# MC-34063.net
KiCad netlist of a schematic drawn in Altium Designer
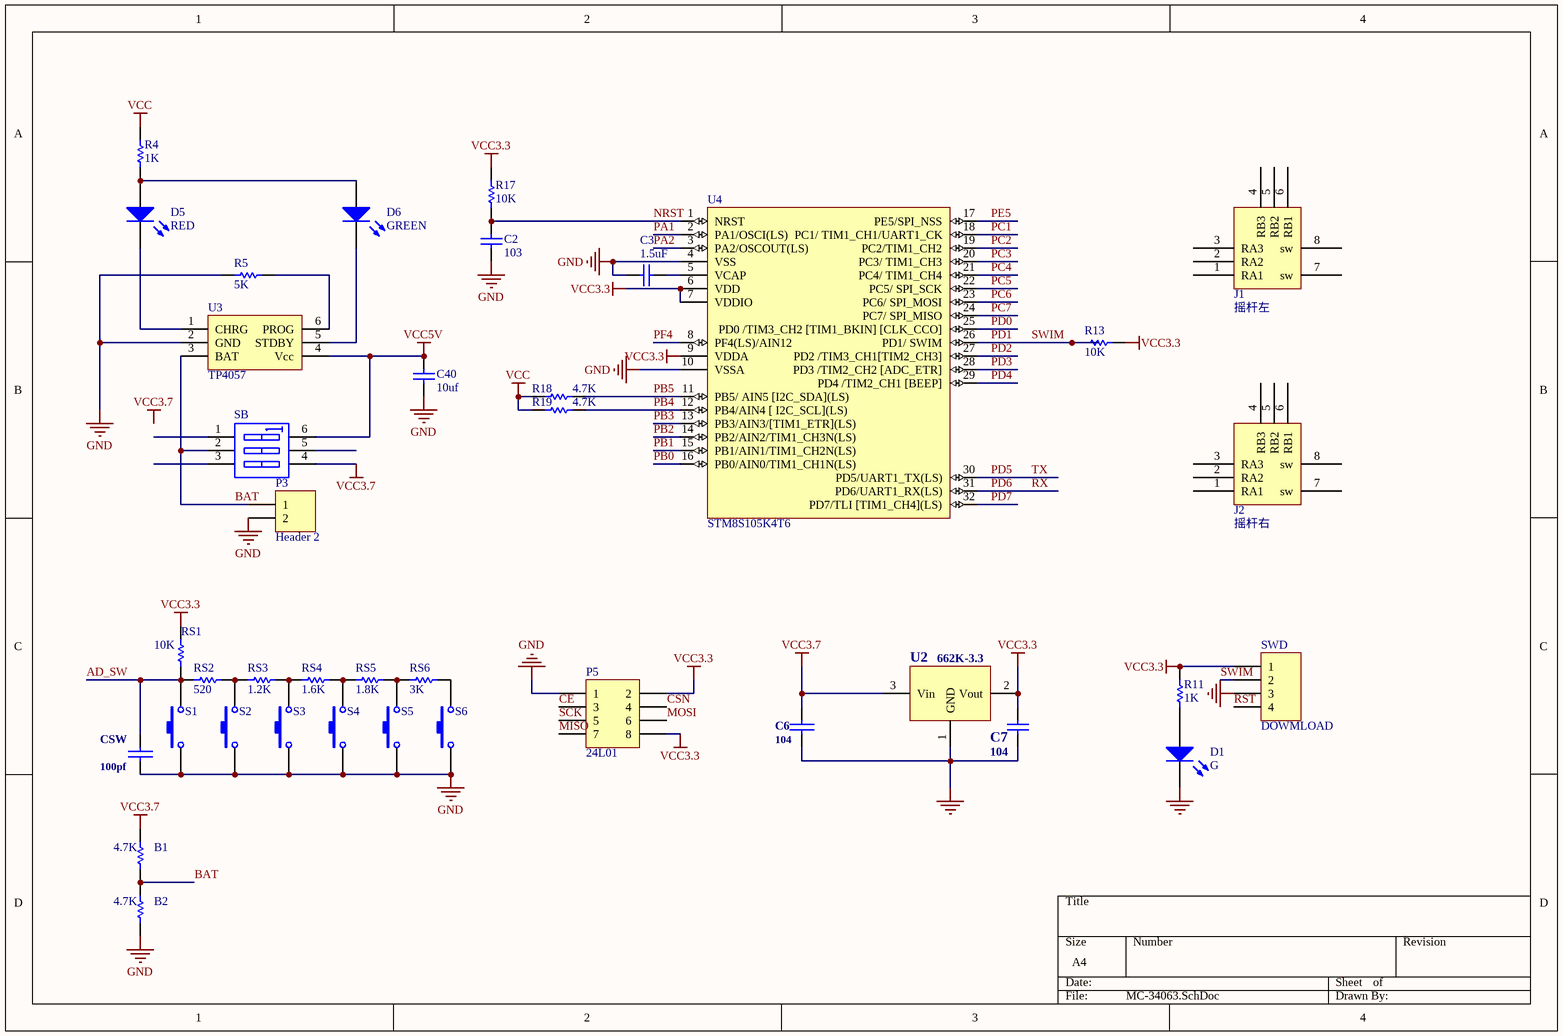
[diagram p0: MC-34063.SchDoc]

(export (version "E")
  (design (tool "Eeschema 10.0.6"))
  (components
    (comp (ref "B1")
      (value "4.7K")
      (footprint "6-0805_L")
      (description "Resistor")
      (fields (field (name "Comment") "Res1") (field (name "PUBLISHER") "Altium Limited"))
      (libsource (lib "Miscellaneous Devices") (part "Res1"))
    )
    (comp (ref "B2")
      (value "4.7K")
      (footprint "6-0805_L")
      (description "Resistor")
      (fields (field (name "Comment") "Res1") (field (name "PUBLISHER") "Altium Limited"))
      (libsource (lib "Miscellaneous Devices") (part "Res1"))
    )
    (comp (ref "C2")
      (value "103")
      (footprint "CAPC2012L")
      (description "Capacitor")
      (fields (field (name "Comment") "Cap") (field (name "PUBLISHER") "Altium Limited"))
      (libsource (lib "Miscellaneous Devices") (part "Cap"))
    )
    (comp (ref "C3")
      (value "1.5uF")
      (footprint "CAPC2012L")
      (description "Capacitor")
      (fields (field (name "Comment") "Cap") (field (name "PUBLISHER") "Altium Limited"))
      (libsource (lib "Miscellaneous Devices") (part "Cap"))
    )
    (comp (ref "C6")
      (value "104")
      (footprint "6-0805_L")
      (description "Capacitor")
      (libsource (lib "*") (part "CAP"))
    )
    (comp (ref "C7")
      (value "104")
      (footprint "6-0805_l")
      (description "Capacitor")
      (libsource (lib "*") (part "Cap"))
    )
    (comp (ref "C40")
      (value "10uf")
      (footprint "CAPC2012L")
      (description "Capacitor")
      (fields (field (name "Comment") "Cap") (field (name "PUBLISHER") "Altium Limited"))
      (libsource (lib "Miscellaneous Devices") (part "Cap"))
    )
    (comp (ref "CSW")
      (value "100pf")
      (footprint "6-0805_L")
      (description "Capacitor")
      (libsource (lib "*") (part "CAP"))
    )
    (comp (ref "D1")
      (value "G")
      (footprint "6-0805_L")
      (description "Typical BLUE SiC LED")
      (fields (field (name "PUBLISHER") "Altium Limited"))
      (libsource (lib "Miscellaneous Devices") (part "LED3"))
    )
    (comp (ref "D5")
      (value "RED")
      (footprint "CD2012-0805")
      (description "Typical BLUE SiC LED")
      (fields (field (name "PUBLISHER") "Altium Limited"))
      (libsource (lib "Miscellaneous Devices") (part "LED3"))
    )
    (comp (ref "D6")
      (value "GREEN")
      (footprint "CD2012-0805")
      (description "Typical BLUE SiC LED")
      (fields (field (name "PUBLISHER") "Altium Limited"))
      (libsource (lib "Miscellaneous Devices") (part "LED3"))
    )
    (comp (ref "J1") (value "摇杆左") (footprint "摇杆") (libsource (lib "摇杆原理图") (part "Component_1")))
    (comp (ref "J2") (value "摇杆右") (footprint "摇杆") (libsource (lib "摇杆原理图") (part "Component_1")))
    (comp (ref "P3")
      (value "Header 2")
      (footprint "HDR1X2")
      (description "Header, 2-Pin")
      (fields (field (name "PUBLISHER") "Altium Limited"))
      (libsource (lib "Miscellaneous Connectors") (part "Header 2"))
    )
    (comp (ref "P5")
      (value "24L01")
      (footprint "HDR2X4")
      (description "Header, 4-Pin, Dual row")
      (fields (field (name "PUBLISHER") "Altium Limited"))
      (libsource (lib "Miscellaneous Connectors") (part "Header 4X2"))
    )
    (comp (ref "R4")
      (value "1K")
      (footprint "RESC2012L")
      (description "Resistor")
      (fields (field (name "Comment") "Res1") (field (name "PUBLISHER") "Altium Limited"))
      (libsource (lib "Miscellaneous Devices") (part "Res1"))
    )
    (comp (ref "R5")
      (value "5K")
      (footprint "RESC2012L")
      (description "Resistor")
      (fields (field (name "Comment") "Res1") (field (name "PUBLISHER") "Altium Limited"))
      (libsource (lib "Miscellaneous Devices") (part "Res1"))
    )
    (comp (ref "R11")
      (value "1K")
      (footprint "6-0805_L")
      (description "Resistor")
      (fields (field (name "Comment") "Res1") (field (name "PUBLISHER") "Altium Limited"))
      (libsource (lib "Miscellaneous Devices") (part "Res1"))
    )
    (comp (ref "R13")
      (value "10K")
      (footprint "6-0805_L")
      (description "Resistor")
      (fields (field (name "Comment") "Res1") (field (name "PUBLISHER") "Altium Limited"))
      (libsource (lib "Miscellaneous Devices") (part "Res1"))
    )
    (comp (ref "R17")
      (value "10K")
      (footprint "RESC2012L")
      (description "Resistor")
      (fields (field (name "Comment") "Res1") (field (name "PUBLISHER") "Altium Limited"))
      (libsource (lib "Miscellaneous Devices") (part "Res1"))
    )
    (comp (ref "R18")
      (value "4.7K")
      (footprint "resc2012l")
      (description "Resistor")
      (fields (field (name "Comment") "Res1") (field (name "PUBLISHER") "Altium Limited"))
      (libsource (lib "Miscellaneous Devices") (part "Res1"))
    )
    (comp (ref "R19")
      (value "4.7K")
      (footprint "resc2012l")
      (description "Resistor")
      (fields (field (name "Comment") "Res1") (field (name "PUBLISHER") "Altium Limited"))
      (libsource (lib "Miscellaneous Devices") (part "Res1"))
    )
    (comp (ref "RS1")
      (value "10K")
      (footprint "6-0805_L")
      (description "Resistor")
      (fields (field (name "Comment") "Res1") (field (name "PUBLISHER") "Altium Limited"))
      (libsource (lib "Miscellaneous Devices") (part "Res1"))
    )
    (comp (ref "RS2")
      (value "520")
      (footprint "6-0805_L")
      (description "Resistor")
      (fields (field (name "Comment") "Res1") (field (name "PUBLISHER") "Altium Limited"))
      (libsource (lib "Miscellaneous Devices") (part "Res1"))
    )
    (comp (ref "RS3")
      (value "1.2K")
      (footprint "6-0805_L")
      (description "Resistor")
      (fields (field (name "Comment") "Res1") (field (name "PUBLISHER") "Altium Limited"))
      (libsource (lib "Miscellaneous Devices") (part "Res1"))
    )
    (comp (ref "RS4")
      (value "1.6K")
      (footprint "6-0805_L")
      (description "Resistor")
      (fields (field (name "Comment") "Res1") (field (name "PUBLISHER") "Altium Limited"))
      (libsource (lib "Miscellaneous Devices") (part "Res1"))
    )
    (comp (ref "RS5")
      (value "1.8K")
      (footprint "6-0805_L")
      (description "Resistor")
      (fields (field (name "Comment") "Res1") (field (name "PUBLISHER") "Altium Limited"))
      (libsource (lib "Miscellaneous Devices") (part "Res1"))
    )
    (comp (ref "RS6")
      (value "3K")
      (footprint "6-0805_L")
      (description "Resistor")
      (fields (field (name "Comment") "Res1") (field (name "PUBLISHER") "Altium Limited"))
      (libsource (lib "Miscellaneous Devices") (part "Res1"))
    )
    (comp (ref "S1")
      (value "SW-PB")
      (footprint "SPST-2")
      (description "Switch")
      (fields (field (name "PUBLISHER") "Altium Limited"))
      (libsource (lib "Miscellaneous Devices") (part "SW-PB"))
    )
    (comp (ref "S2")
      (value "SW-PB")
      (footprint "SPST-2")
      (description "Switch")
      (fields (field (name "PUBLISHER") "Altium Limited"))
      (libsource (lib "Miscellaneous Devices") (part "SW-PB"))
    )
    (comp (ref "S3")
      (value "SW-PB")
      (footprint "SPST-2")
      (description "Switch")
      (fields (field (name "PUBLISHER") "Altium Limited"))
      (libsource (lib "Miscellaneous Devices") (part "SW-PB"))
    )
    (comp (ref "S4")
      (value "SW-PB")
      (footprint "SPST-2")
      (description "Switch")
      (fields (field (name "PUBLISHER") "Altium Limited"))
      (libsource (lib "Miscellaneous Devices") (part "SW-PB"))
    )
    (comp (ref "S5")
      (value "SW-PB")
      (footprint "SPST-2")
      (description "Switch")
      (fields (field (name "PUBLISHER") "Altium Limited"))
      (libsource (lib "Miscellaneous Devices") (part "SW-PB"))
    )
    (comp (ref "S6")
      (value "SW-PB")
      (footprint "SPST-2")
      (description "Switch")
      (fields (field (name "PUBLISHER") "Altium Limited"))
      (libsource (lib "Miscellaneous Devices") (part "SW-PB"))
    )
    (comp (ref "SB")
      (value "SW DIP-3")
      (footprint "sw-slk")
      (description "DIP Switch, 3 Position, SPST")
      (fields (field (name "PUBLISHER") "Altium Limited"))
      (libsource (lib "Miscellaneous Devices") (part "SW DIP-3"))
    )
    (comp (ref "SWD")
      (value "DOWMLOAD")
      (footprint "HDR1X4")
      (description "Header, 4-Pin")
      (fields (field (name "PUBLISHER") "Altium Limited"))
      (libsource (lib "Miscellaneous Connectors") (part "Header 4"))
    )
    (comp (ref "U2")
      (value "662K-3.3")
      (footprint "SOT-23_L")
      (description "three terminal regulator")
      (libsource (lib "*") (part "78MXX"))
    )
    (comp (ref "U3")
      (value "TP4057")
      (footprint "SOT23-6_L")
      (description "500mA单节锂离子电池充电器")
      (libsource (lib "My") (part "TP4057"))
    )
    (comp (ref "U4")
      (value "STM8S105K4T6")
      (footprint "LQLPF32")
      (description "STM8 Microcontroller with 16K Bytes Flash Memory 32PIN LQFP32")
      (fields (field (name "PUBLISHER") "Altium Limited"))
      (libsource (lib "stm8STM32AVR") (part "STM8S105K4T6"))
    )
  )
  (nets
    (net (code "1") (name "/AD_SW") (class "Default")
      (node (ref "CSW") (pin "1") (pinfunction "1_1") (pintype "passive"))
      (node (ref "RS1") (pin "1") (pinfunction "1_1") (pintype "passive"))
      (node (ref "RS2") (pin "2") (pinfunction "2_2") (pintype "passive"))
      (node (ref "S1") (pin "2") (pinfunction "2_2") (pintype "passive"))
    )
    (net (code "2") (name "/BAT") (class "Default")
      (node (ref "B1") (pin "1") (pinfunction "1_1") (pintype "passive"))
      (node (ref "B2") (pin "2") (pinfunction "2_2") (pintype "passive"))
      (node (ref "P3") (pin "1") (pinfunction "1_1") (pintype "passive"))
      (node (ref "SB") (pin "2") (pinfunction "A2_2") (pintype "passive"))
      (node (ref "U3") (pin "3") (pinfunction "BAT_3") (pintype "passive"))
    )
    (net (code "3") (name "/CE") (class "Default")
      (node (ref "P5") (pin "3") (pinfunction "3_3") (pintype "passive"))
    )
    (net (code "4") (name "/CSN") (class "Default")
      (node (ref "P5") (pin "4") (pinfunction "4_4") (pintype "passive"))
    )
    (net (code "5") (name "/MISO") (class "Default")
      (node (ref "P5") (pin "7") (pinfunction "7_7") (pintype "passive"))
    )
    (net (code "6") (name "/MOSI") (class "Default")
      (node (ref "P5") (pin "6") (pinfunction "6_6") (pintype "passive"))
    )
    (net (code "7") (name "/NRST") (class "Default")
      (node (ref "C2") (pin "2") (pinfunction "2_2") (pintype "passive"))
      (node (ref "R17") (pin "1") (pinfunction "1_1") (pintype "passive"))
      (node (ref "U4") (pin "1") (pinfunction "NRST_1") (pintype "bidirectional"))
    )
    (net (code "8") (name "/PA1") (class "Default")
      (node (ref "U4") (pin "2") (pinfunction "PA1/OSCI(LS)_2") (pintype "bidirectional"))
    )
    (net (code "9") (name "/PA2") (class "Default")
      (node (ref "U4") (pin "3") (pinfunction "PA2/OSCOUT(LS)_3") (pintype "bidirectional"))
    )
    (net (code "10") (name "/PB0") (class "Default")
      (node (ref "U4") (pin "16") (pinfunction "PB0/AIN0/TIM1_CH1N(LS)_16") (pintype "bidirectional"))
    )
    (net (code "11") (name "/PB1") (class "Default")
      (node (ref "U4") (pin "15") (pinfunction "PB1/AIN1/TIM1_CH2N(LS)_15") (pintype "bidirectional"))
    )
    (net (code "12") (name "/PB2") (class "Default")
      (node (ref "U4") (pin "14") (pinfunction "PB2/AIN2/TIM1_CH3N(LS)_14") (pintype "bidirectional"))
    )
    (net (code "13") (name "/PB3") (class "Default")
      (node (ref "U4") (pin "13") (pinfunction "PB3/AIN3/[TIM1_ETR](LS)_13") (pintype "bidirectional"))
    )
    (net (code "14") (name "/PB4") (class "Default")
      (node (ref "R19") (pin "1") (pinfunction "1_1") (pintype "passive"))
      (node (ref "U4") (pin "12") (pinfunction "PB4/AIN4_[_I2C_SCL](LS)_12") (pintype "bidirectional"))
    )
    (net (code "15") (name "/PB5") (class "Default")
      (node (ref "R18") (pin "1") (pinfunction "1_1") (pintype "passive"))
      (node (ref "U4") (pin "11") (pinfunction "PB5/_AIN5_[I2C_SDA](LS)_11") (pintype "bidirectional"))
    )
    (net (code "16") (name "/PC1") (class "Default")
      (node (ref "U4") (pin "18") (pinfunction "PC1/_TIM1_CH1/UART1_CK_18") (pintype "bidirectional"))
    )
    (net (code "17") (name "/PC2") (class "Default")
      (node (ref "U4") (pin "19") (pinfunction "PC2/TIM1_CH2_19") (pintype "bidirectional"))
    )
    (net (code "18") (name "/PC3") (class "Default")
      (node (ref "U4") (pin "20") (pinfunction "PC3/_TIM1_CH3_20") (pintype "bidirectional"))
    )
    (net (code "19") (name "/PC4") (class "Default")
      (node (ref "U4") (pin "21") (pinfunction "PC4/_TIM1_CH4_21") (pintype "bidirectional"))
    )
    (net (code "20") (name "/PC5") (class "Default")
      (node (ref "U4") (pin "22") (pinfunction "PC5/_SPI_SCK_22") (pintype "bidirectional"))
    )
    (net (code "21") (name "/PC6") (class "Default")
      (node (ref "U4") (pin "23") (pinfunction "PC6/_SPI_MOSI_23") (pintype "bidirectional"))
    )
    (net (code "22") (name "/PC7") (class "Default")
      (node (ref "U4") (pin "24") (pinfunction "PC7/_SPI_MISO_24") (pintype "bidirectional"))
    )
    (net (code "23") (name "/PD0") (class "Default")
      (node (ref "U4") (pin "25") (pinfunction "PD0_/TIM3_CH2_[TIM1_BKIN]_[CLK_CCO]_25") (pintype "bidirectional"))
    )
    (net (code "24") (name "/PD1") (class "Default")
      (node (ref "R13") (pin "1") (pinfunction "1_1") (pintype "passive"))
      (node (ref "SWD") (pin "2") (pinfunction "2_2") (pintype "passive"))
      (node (ref "U4") (pin "26") (pinfunction "PD1/_SWIM_26") (pintype "bidirectional"))
    )
    (net (code "25") (name "/PD2") (class "Default")
      (node (ref "U4") (pin "27") (pinfunction "PD2_/TIM3_CH1[TIM2_CH3]_27") (pintype "bidirectional"))
    )
    (net (code "26") (name "/PD3") (class "Default")
      (node (ref "U4") (pin "28") (pinfunction "PD3_/TIM2_CH2_[ADC_ETR]_28") (pintype "bidirectional"))
    )
    (net (code "27") (name "/PD4") (class "Default")
      (node (ref "U4") (pin "29") (pinfunction "PD4_/TIM2_CH1_[BEEP]_29") (pintype "bidirectional"))
    )
    (net (code "28") (name "/PD5") (class "Default")
      (node (ref "U4") (pin "30") (pinfunction "PD5/UART1_TX(LS)_30") (pintype "bidirectional"))
    )
    (net (code "29") (name "/PD6") (class "Default")
      (node (ref "U4") (pin "31") (pinfunction "PD6/UART1_RX(LS)_31") (pintype "bidirectional"))
    )
    (net (code "30") (name "/PD7") (class "Default")
      (node (ref "U4") (pin "32") (pinfunction "PD7/TLI_[TIM1_CH4](LS)_32") (pintype "bidirectional"))
    )
    (net (code "31") (name "/PE5") (class "Default")
      (node (ref "U4") (pin "17") (pinfunction "PE5/SPI_NSS_17") (pintype "bidirectional"))
    )
    (net (code "32") (name "/PF4") (class "Default")
      (node (ref "U4") (pin "8") (pinfunction "PF4(LS)/AIN12_8") (pintype "bidirectional"))
    )
    (net (code "33") (name "/RST") (class "Default")
      (node (ref "SWD") (pin "4") (pinfunction "4_4") (pintype "passive"))
    )
    (net (code "34") (name "/SCK") (class "Default")
      (node (ref "P5") (pin "5") (pinfunction "5_5") (pintype "passive"))
    )
    (net (code "35") (name "GND") (class "Default")
      (node (ref "B2") (pin "1") (pinfunction "1_1") (pintype "passive"))
      (node (ref "C2") (pin "1") (pinfunction "1_1") (pintype "passive"))
      (node (ref "C3") (pin "2") (pinfunction "2_2") (pintype "passive"))
      (node (ref "C40") (pin "1") (pinfunction "1_1") (pintype "passive"))
      (node (ref "C6") (pin "2") (pinfunction "2_2") (pintype "passive"))
      (node (ref "C7") (pin "1") (pinfunction "1_1") (pintype "passive"))
      (node (ref "CSW") (pin "2") (pinfunction "2_2") (pintype "passive"))
      (node (ref "D1") (pin "2") (pinfunction "K_2") (pintype "passive"))
      (node (ref "P3") (pin "2") (pinfunction "2_2") (pintype "passive"))
      (node (ref "P5") (pin "1") (pinfunction "1_1") (pintype "passive"))
      (node (ref "R5") (pin "2") (pinfunction "2_2") (pintype "passive"))
      (node (ref "S1") (pin "1") (pinfunction "1_1") (pintype "passive"))
      (node (ref "S2") (pin "1") (pinfunction "1_1") (pintype "passive"))
      (node (ref "S3") (pin "1") (pinfunction "1_1") (pintype "passive"))
      (node (ref "S4") (pin "1") (pinfunction "1_1") (pintype "passive"))
      (node (ref "S5") (pin "1") (pinfunction "1_1") (pintype "passive"))
      (node (ref "S6") (pin "1") (pinfunction "1_1") (pintype "passive"))
      (node (ref "SWD") (pin "3") (pinfunction "3_3") (pintype "passive"))
      (node (ref "U2") (pin "1") (pinfunction "GND_1") (pintype "passive"))
      (node (ref "U3") (pin "2") (pinfunction "GND_2") (pintype "passive"))
      (node (ref "U4") (pin "10") (pinfunction "VSSA_10") (pintype "power_in"))
      (node (ref "U4") (pin "4") (pinfunction "VSS_4") (pintype "power_in"))
    )
    (net (code "36") (name "Net-(D1-A)") (class "Default")
      (node (ref "D1") (pin "1") (pinfunction "A_1") (pintype "passive"))
      (node (ref "R11") (pin "1") (pinfunction "1_1") (pintype "passive"))
    )
    (net (code "37") (name "Net-(D5-A)") (class "Default")
      (node (ref "D5") (pin "1") (pinfunction "A_1") (pintype "passive"))
      (node (ref "D6") (pin "1") (pinfunction "A_1") (pintype "passive"))
      (node (ref "R4") (pin "1") (pinfunction "1_1") (pintype "passive"))
    )
    (net (code "38") (name "Net-(D5-K)") (class "Default")
      (node (ref "D5") (pin "2") (pinfunction "K_2") (pintype "passive"))
      (node (ref "U3") (pin "1") (pinfunction "CHRG_1") (pintype "passive"))
    )
    (net (code "39") (name "Net-(D6-K)") (class "Default")
      (node (ref "D6") (pin "2") (pinfunction "K_2") (pintype "passive"))
      (node (ref "U3") (pin "5") (pinfunction "STDBY_5") (pintype "passive"))
    )
    (net (code "40") (name "Net-(RS2-Pad1)") (class "Default")
      (node (ref "RS2") (pin "1") (pinfunction "1_1") (pintype "passive"))
      (node (ref "RS3") (pin "2") (pinfunction "2_2") (pintype "passive"))
      (node (ref "S2") (pin "2") (pinfunction "2_2") (pintype "passive"))
    )
    (net (code "41") (name "Net-(RS3-Pad1)") (class "Default")
      (node (ref "RS3") (pin "1") (pinfunction "1_1") (pintype "passive"))
      (node (ref "RS4") (pin "2") (pinfunction "2_2") (pintype "passive"))
      (node (ref "S3") (pin "2") (pinfunction "2_2") (pintype "passive"))
    )
    (net (code "42") (name "Net-(RS4-Pad1)") (class "Default")
      (node (ref "RS4") (pin "1") (pinfunction "1_1") (pintype "passive"))
      (node (ref "RS5") (pin "2") (pinfunction "2_2") (pintype "passive"))
      (node (ref "S4") (pin "2") (pinfunction "2_2") (pintype "passive"))
    )
    (net (code "43") (name "Net-(RS5-Pad1)") (class "Default")
      (node (ref "RS5") (pin "1") (pinfunction "1_1") (pintype "passive"))
      (node (ref "RS6") (pin "2") (pinfunction "2_2") (pintype "passive"))
      (node (ref "S5") (pin "2") (pinfunction "2_2") (pintype "passive"))
    )
    (net (code "44") (name "Net-(RS6-Pad1)") (class "Default")
      (node (ref "RS6") (pin "1") (pinfunction "1_1") (pintype "passive"))
      (node (ref "S6") (pin "2") (pinfunction "2_2") (pintype "passive"))
    )
    (net (code "45") (name "Net-(U3-PROG)") (class "Default")
      (node (ref "R5") (pin "1") (pinfunction "1_1") (pintype "passive"))
      (node (ref "U3") (pin "6") (pinfunction "PROG_6") (pintype "passive"))
    )
    (net (code "46") (name "Net-(U4-VCAP)") (class "Default")
      (node (ref "C3") (pin "1") (pinfunction "1_1") (pintype "passive"))
      (node (ref "U4") (pin "5") (pinfunction "VCAP_5") (pintype "power_in"))
    )
    (net (code "47") (name "VCC") (class "Default")
      (node (ref "R18") (pin "2") (pinfunction "2_2") (pintype "passive"))
      (node (ref "R19") (pin "2") (pinfunction "2_2") (pintype "passive"))
      (node (ref "R4") (pin "2") (pinfunction "2_2") (pintype "passive"))
    )
    (net (code "48") (name "VCC3.3") (class "Default")
      (node (ref "C7") (pin "2") (pinfunction "2_2") (pintype "passive"))
      (node (ref "P5") (pin "2") (pinfunction "2_2") (pintype "passive"))
      (node (ref "P5") (pin "8") (pinfunction "8_8") (pintype "passive"))
      (node (ref "R11") (pin "2") (pinfunction "2_2") (pintype "passive"))
      (node (ref "R13") (pin "2") (pinfunction "2_2") (pintype "passive"))
      (node (ref "R17") (pin "2") (pinfunction "2_2") (pintype "passive"))
      (node (ref "RS1") (pin "2") (pinfunction "2_2") (pintype "passive"))
      (node (ref "SWD") (pin "1") (pinfunction "1_1") (pintype "passive"))
      (node (ref "U2") (pin "2") (pinfunction "Vout_2") (pintype "passive"))
      (node (ref "U4") (pin "6") (pinfunction "VDD_6") (pintype "power_in"))
      (node (ref "U4") (pin "7") (pinfunction "VDDIO_7") (pintype "power_in"))
      (node (ref "U4") (pin "9") (pinfunction "VDDA_9") (pintype "power_in"))
    )
    (net (code "49") (name "VCC3.7") (class "Default")
      (node (ref "B1") (pin "2") (pinfunction "2_2") (pintype "passive"))
      (node (ref "C6") (pin "1") (pinfunction "1_1") (pintype "passive"))
      (node (ref "SB") (pin "4") (pinfunction "B3_4") (pintype "passive"))
      (node (ref "U2") (pin "3") (pinfunction "Vin_3") (pintype "passive"))
    )
    (net (code "50") (name "VCC5V") (class "Default")
      (node (ref "C40") (pin "2") (pinfunction "2_2") (pintype "passive"))
      (node (ref "SB") (pin "6") (pinfunction "B1_6") (pintype "passive"))
      (node (ref "U3") (pin "4") (pinfunction "Vcc_4") (pintype "passive"))
    )
    (net (code "51") (name "unconnected-(J1-RA1-Pad1)") (class "Default")
      (node (ref "J1") (pin "1") (pinfunction "RA1_1") (pintype "passive"))
    )
    (net (code "52") (name "unconnected-(J1-RA2-Pad2)") (class "Default")
      (node (ref "J1") (pin "2") (pinfunction "RA2_2") (pintype "passive"))
    )
    (net (code "53") (name "unconnected-(J1-RA3-Pad3)") (class "Default")
      (node (ref "J1") (pin "3") (pinfunction "RA3_3") (pintype "passive"))
    )
    (net (code "54") (name "unconnected-(J1-RB1-Pad6)") (class "Default")
      (node (ref "J1") (pin "6") (pinfunction "RB1_6") (pintype "passive"))
    )
    (net (code "55") (name "unconnected-(J1-RB2-Pad5)") (class "Default")
      (node (ref "J1") (pin "5") (pinfunction "RB2_5") (pintype "passive"))
    )
    (net (code "56") (name "unconnected-(J1-RB3-Pad4)") (class "Default")
      (node (ref "J1") (pin "4") (pinfunction "RB3_4") (pintype "passive"))
    )
    (net (code "57") (name "unconnected-(J1-sw-Pad7)") (class "Default")
      (node (ref "J1") (pin "7") (pinfunction "sw_7") (pintype "passive"))
    )
    (net (code "58") (name "unconnected-(J1-sw-Pad8)") (class "Default")
      (node (ref "J1") (pin "8") (pinfunction "sw_8") (pintype "passive"))
    )
    (net (code "59") (name "unconnected-(J2-RA1-Pad1)") (class "Default")
      (node (ref "J2") (pin "1") (pinfunction "RA1_1") (pintype "passive"))
    )
    (net (code "60") (name "unconnected-(J2-RA2-Pad2)") (class "Default")
      (node (ref "J2") (pin "2") (pinfunction "RA2_2") (pintype "passive"))
    )
    (net (code "61") (name "unconnected-(J2-RA3-Pad3)") (class "Default")
      (node (ref "J2") (pin "3") (pinfunction "RA3_3") (pintype "passive"))
    )
    (net (code "62") (name "unconnected-(J2-RB1-Pad6)") (class "Default")
      (node (ref "J2") (pin "6") (pinfunction "RB1_6") (pintype "passive"))
    )
    (net (code "63") (name "unconnected-(J2-RB2-Pad5)") (class "Default")
      (node (ref "J2") (pin "5") (pinfunction "RB2_5") (pintype "passive"))
    )
    (net (code "64") (name "unconnected-(J2-RB3-Pad4)") (class "Default")
      (node (ref "J2") (pin "4") (pinfunction "RB3_4") (pintype "passive"))
    )
    (net (code "65") (name "unconnected-(J2-sw-Pad7)") (class "Default")
      (node (ref "J2") (pin "7") (pinfunction "sw_7") (pintype "passive"))
    )
    (net (code "66") (name "unconnected-(J2-sw-Pad8)") (class "Default")
      (node (ref "J2") (pin "8") (pinfunction "sw_8") (pintype "passive"))
    )
    (net (code "67") (name "unconnected-(SB-A1-Pad1)") (class "Default")
      (node (ref "SB") (pin "1") (pinfunction "A1_1") (pintype "passive"))
    )
    (net (code "68") (name "unconnected-(SB-A3-Pad3)") (class "Default")
      (node (ref "SB") (pin "3") (pinfunction "A3_3") (pintype "passive"))
    )
    (net (code "69") (name "unconnected-(SB-B2-Pad5)") (class "Default")
      (node (ref "SB") (pin "5") (pinfunction "B2_5") (pintype "passive"))
    )
  )
)
